# main.net
KiCad netlist of a schematic drawn in EAGLE
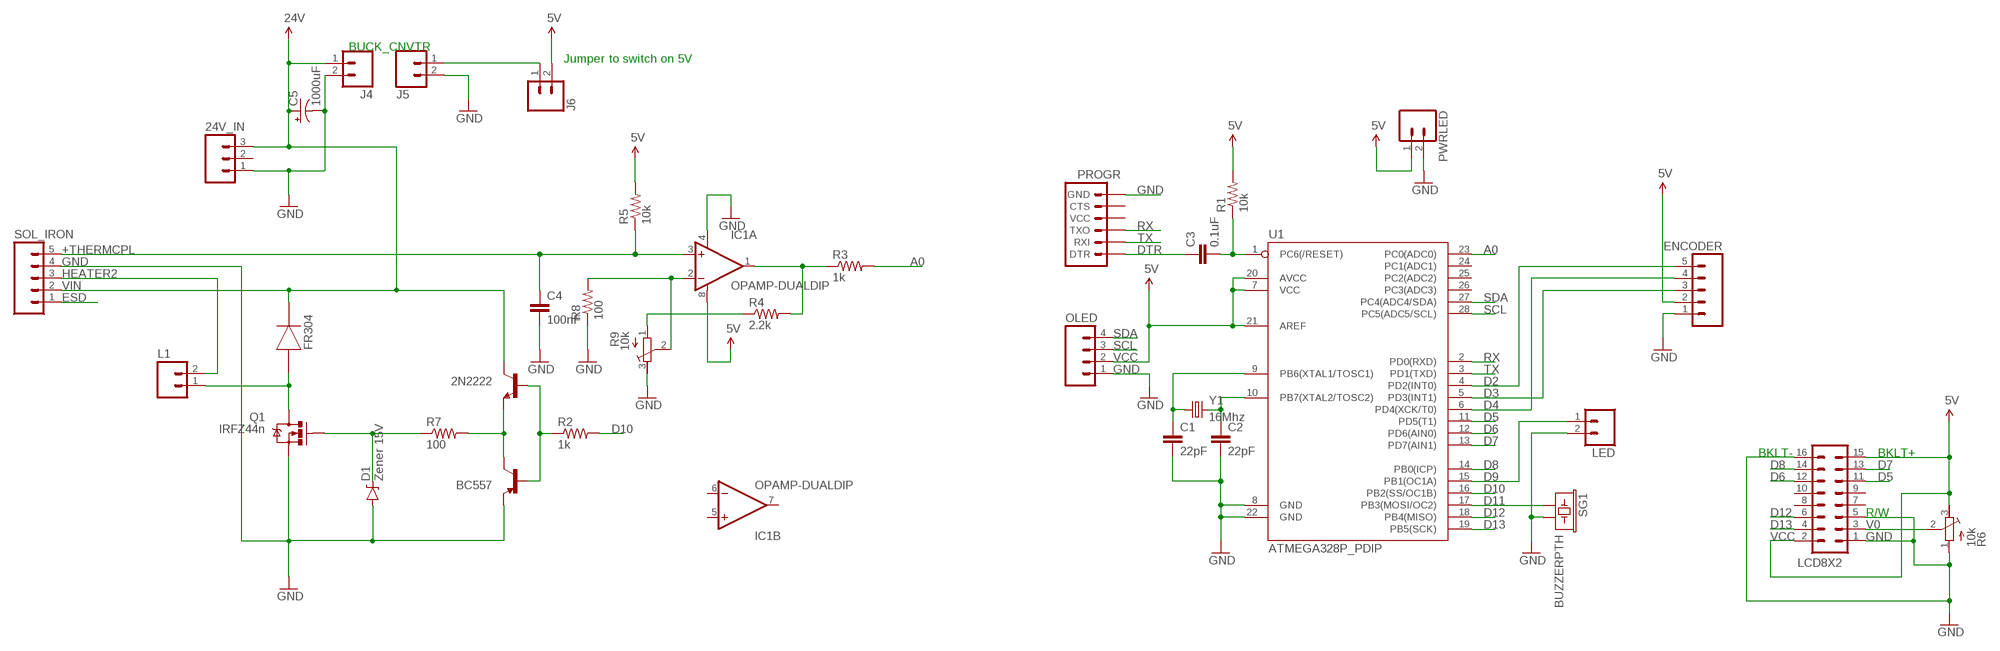
[diagram p0: schematic, sheet 1]

(export (version "E")
  (design (tool "Eeschema 10.0.6"))
  (components
    (comp (ref "2N2222")
      (value "TRANSISTOR_NPNP2N2222A")
      (footprint "eagle-import:TO-92")
      (libsource (lib "eagle-import") (part "TRANSISTOR_NPNP2N2222A"))
    )
    (comp (ref "24V_IN")
      (value "M03PTH")
      (footprint "eagle-import:1X03")
      (libsource (lib "eagle-import") (part "M03PTH"))
    )
    (comp (ref "BC557")
      (value "TRANSISTOR_PNPTO92")
      (footprint "eagle-import:TO-92")
      (libsource (lib "eagle-import") (part "TRANSISTOR_PNPTO92"))
    )
    (comp (ref "C1")
      (value "22pF")
      (footprint "eagle-import:CAP-PTH-SMALL")
      (libsource (lib "eagle-import") (part "CAPPTH"))
    )
    (comp (ref "C2")
      (value "22pF")
      (footprint "eagle-import:CAP-PTH-SMALL")
      (libsource (lib "eagle-import") (part "CAPPTH"))
    )
    (comp (ref "C3")
      (value "0.1uF")
      (footprint "eagle-import:CAP-PTH-SMALL")
      (libsource (lib "eagle-import") (part "CAPPTH"))
    )
    (comp (ref "C4")
      (value "100nF")
      (footprint "eagle-import:CAP-PTH-SMALL")
      (libsource (lib "eagle-import") (part "CAPPTH"))
    )
    (comp (ref "C5")
      (value "1000uF")
      (footprint "eagle-import:CPOL-RADIAL-1000UF-25V")
      (libsource (lib "eagle-import") (part "CAP_POLPTH4"))
    )
    (comp (ref "D1")
      (value "Zener 15V")
      (footprint "eagle-import:DIODE-ZENER")
      (libsource (lib "eagle-import") (part "DIODE-ZENERPTH"))
    )
    (comp (ref "ENCODER")
      (value "M05PTH")
      (footprint "eagle-import:1X05")
      (libsource (lib "eagle-import") (part "M05PTH"))
    )
    (comp (ref "IC1")
      (value "OPAMP-DUALDIP")
      (footprint "eagle-import:DIP08")
      (libsource (lib "eagle-import") (part "OPAMP-DUALDIP"))
    )
    (comp (ref "J4")
      (value "M02PTH")
      (footprint "eagle-import:1X02")
      (libsource (lib "eagle-import") (part "M02PTH"))
    )
    (comp (ref "J5")
      (value "M02PTH")
      (footprint "eagle-import:1X02")
      (libsource (lib "eagle-import") (part "M02PTH"))
    )
    (comp (ref "J6")
      (value "M02PTH")
      (footprint "eagle-import:1X02")
      (libsource (lib "eagle-import") (part "M02PTH"))
    )
    (comp (ref "L1")
      (value "M02PTH")
      (footprint "eagle-import:1X02")
      (libsource (lib "eagle-import") (part "M02PTH"))
    )
    (comp (ref "LCD8X2")
      (value "M08X2")
      (footprint "eagle-import:2X8")
      (libsource (lib "eagle-import") (part "M08X2"))
    )
    (comp (ref "LED")
      (value "M02PTH")
      (footprint "eagle-import:1X02")
      (libsource (lib "eagle-import") (part "M02PTH"))
    )
    (comp (ref "OLED")
      (value "M04PTH")
      (footprint "eagle-import:1X04")
      (libsource (lib "eagle-import") (part "M04PTH"))
    )
    (comp (ref "PROGR")
      (value "ARDUINO_SERIAL_PROGRAMPTH")
      (footprint "eagle-import:1X06")
      (libsource (lib "eagle-import") (part "ARDUINO_SERIAL_PROGRAMPTH"))
    )
    (comp (ref "PWRLED")
      (value "M02PTH")
      (footprint "eagle-import:1X02")
      (libsource (lib "eagle-import") (part "M02PTH"))
    )
    (comp (ref "Q1")
      (value "IRFZ44n")
      (footprint "eagle-import:TO220V")
      (libsource (lib "eagle-import") (part "MOSFET-NCHANNELFQP30N06L"))
    )
    (comp (ref "R1")
      (value "10k")
      (footprint "eagle-import:AXIAL-0.4")
      (libsource (lib "eagle-import") (part "RESISTORPTH-1/4W"))
    )
    (comp (ref "R2")
      (value "1k")
      (footprint "eagle-import:AXIAL-0.4")
      (libsource (lib "eagle-import") (part "RESISTORPTH-1/4W"))
    )
    (comp (ref "R3")
      (value "1k")
      (footprint "eagle-import:AXIAL-0.4")
      (libsource (lib "eagle-import") (part "RESISTORPTH-1/4W"))
    )
    (comp (ref "R4")
      (value "2.2k")
      (footprint "eagle-import:AXIAL-0.4")
      (libsource (lib "eagle-import") (part "RESISTORPTH-1/4W"))
    )
    (comp (ref "R5")
      (value "10k")
      (footprint "eagle-import:AXIAL-0.4")
      (libsource (lib "eagle-import") (part "RESISTORPTH-1/4W"))
    )
    (comp (ref "R6")
      (value "10k")
      (footprint "eagle-import:RTRIM3296W")
      (libsource (lib "eagle-import") (part "R-TRIMM3296W"))
    )
    (comp (ref "R7")
      (value "100")
      (footprint "eagle-import:AXIAL-0.4")
      (libsource (lib "eagle-import") (part "RESISTORPTH-1/4W"))
    )
    (comp (ref "R8")
      (value "100")
      (footprint "eagle-import:AXIAL-0.4")
      (libsource (lib "eagle-import") (part "RESISTORPTH-1/4W"))
    )
    (comp (ref "R9")
      (value "10k")
      (footprint "eagle-import:RTRIM3296W")
      (libsource (lib "eagle-import") (part "R-TRIMM3296W"))
    )
    (comp (ref "SG1")
      (value "BUZZERPTH")
      (footprint "eagle-import:BUZZER-12MM")
      (libsource (lib "eagle-import") (part "BUZZERPTH"))
    )
    (comp (ref "SOL_IRON")
      (value "M05PTH")
      (footprint "eagle-import:1X05")
      (libsource (lib "eagle-import") (part "M05PTH"))
    )
    (comp (ref "U$1")
      (value "FR304")
      (footprint "eagle-import:FR304")
      (libsource (lib "eagle-import") (part "FR304"))
    )
    (comp (ref "U1")
      (value "ATMEGA328P_PDIP")
      (footprint "eagle-import:DIL28-3")
      (libsource (lib "eagle-import") (part "ATMEGA328P_PDIP"))
    )
    (comp (ref "Y1")
      (value "16Mhz")
      (footprint "eagle-import:HC49US")
      (libsource (lib "eagle-import") (part "CRYSTALHC49US"))
    )
  )
  (nets
    (net (code "1") (name "/+THERMCPL") (class "Default")
      (node (ref "C4") (pin "1") (pinfunction "1_1") (pintype "passive"))
      (node (ref "IC1") (pin "3") (pinfunction "+IN_3") (pintype "input"))
      (node (ref "R5") (pin "P$1") (pinfunction "1_P$1") (pintype "passive"))
      (node (ref "SOL_IRON") (pin "5") (pinfunction "5_5") (pintype "passive"))
    )
    (net (code "2") (name "/A0") (class "Default")
      (node (ref "R3") (pin "P$2") (pinfunction "2_P$2") (pintype "passive"))
      (node (ref "U1") (pin "23") (pinfunction "PC0(ADC0)_23") (pintype "bidirectional"))
    )
    (net (code "3") (name "/D2") (class "Default")
      (node (ref "ENCODER") (pin "5") (pinfunction "5_5") (pintype "passive"))
      (node (ref "U1") (pin "4") (pinfunction "PD2(INT0)_4") (pintype "bidirectional"))
    )
    (net (code "4") (name "/D3") (class "Default")
      (node (ref "ENCODER") (pin "3") (pinfunction "3_3") (pintype "passive"))
      (node (ref "U1") (pin "5") (pinfunction "PD3(INT1)_5") (pintype "bidirectional"))
    )
    (net (code "5") (name "/D4") (class "Default")
      (node (ref "ENCODER") (pin "4") (pinfunction "4_4") (pintype "passive"))
      (node (ref "U1") (pin "6") (pinfunction "PD4(XCK/T0)_6") (pintype "bidirectional"))
    )
    (net (code "6") (name "/D5") (class "Default")
      (node (ref "LCD8X2") (pin "11") (pinfunction "11_11") (pintype "passive"))
      (node (ref "U1") (pin "11") (pinfunction "PD5(T1)_11") (pintype "bidirectional"))
    )
    (net (code "7") (name "/D6") (class "Default")
      (node (ref "LCD8X2") (pin "12") (pinfunction "12_12") (pintype "passive"))
      (node (ref "U1") (pin "12") (pinfunction "PD6(AIN0)_12") (pintype "bidirectional"))
    )
    (net (code "8") (name "/D7") (class "Default")
      (node (ref "LCD8X2") (pin "13") (pinfunction "13_13") (pintype "passive"))
      (node (ref "U1") (pin "13") (pinfunction "PD7(AIN1)_13") (pintype "bidirectional"))
    )
    (net (code "9") (name "/D8") (class "Default")
      (node (ref "LCD8X2") (pin "14") (pinfunction "14_14") (pintype "passive"))
      (node (ref "U1") (pin "14") (pinfunction "PB0(ICP)_14") (pintype "bidirectional"))
    )
    (net (code "10") (name "/D9") (class "Default")
      (node (ref "LED") (pin "1") (pinfunction "1_1") (pintype "passive"))
      (node (ref "U1") (pin "15") (pinfunction "PB1(OC1A)_15") (pintype "bidirectional"))
    )
    (net (code "11") (name "/D10") (class "Default")
      (node (ref "R2") (pin "P$2") (pinfunction "2_P$2") (pintype "passive"))
      (node (ref "U1") (pin "16") (pinfunction "PB2(SS/OC1B)_16") (pintype "bidirectional"))
    )
    (net (code "12") (name "/D11") (class "Default")
      (node (ref "SG1") (pin "+") (pinfunction "1_+") (pintype "passive"))
      (node (ref "U1") (pin "17") (pinfunction "PB3(MOSI/OC2)_17") (pintype "bidirectional"))
    )
    (net (code "13") (name "/D12") (class "Default")
      (node (ref "LCD8X2") (pin "6") (pinfunction "6_6") (pintype "passive"))
      (node (ref "U1") (pin "18") (pinfunction "PB4(MISO)_18") (pintype "bidirectional"))
    )
    (net (code "14") (name "/D13") (class "Default")
      (node (ref "LCD8X2") (pin "4") (pinfunction "4_4") (pintype "passive"))
      (node (ref "U1") (pin "19") (pinfunction "PB5(SCK)_19") (pintype "bidirectional"))
    )
    (net (code "15") (name "/DTR") (class "Default")
      (node (ref "C3") (pin "1") (pinfunction "1_1") (pintype "passive"))
      (node (ref "PROGR") (pin "1") (pinfunction "DTR_1") (pintype "passive"))
    )
    (net (code "16") (name "/ESD") (class "Default")
      (node (ref "SOL_IRON") (pin "1") (pinfunction "1_1") (pintype "passive"))
    )
    (net (code "17") (name "/HEATER2") (class "Default")
      (node (ref "L1") (pin "2") (pinfunction "2_2") (pintype "passive"))
      (node (ref "SOL_IRON") (pin "3") (pinfunction "3_3") (pintype "passive"))
    )
    (net (code "18") (name "/RX") (class "Default")
      (node (ref "PROGR") (pin "3") (pinfunction "TXO_3") (pintype "passive"))
      (node (ref "U1") (pin "2") (pinfunction "PD0(RXD)_2") (pintype "bidirectional"))
    )
    (net (code "19") (name "/SCL") (class "Default")
      (node (ref "OLED") (pin "3") (pinfunction "3_3") (pintype "passive"))
      (node (ref "U1") (pin "28") (pinfunction "PC5(ADC5/SCL)_28") (pintype "bidirectional"))
    )
    (net (code "20") (name "/SDA") (class "Default")
      (node (ref "OLED") (pin "4") (pinfunction "4_4") (pintype "passive"))
      (node (ref "U1") (pin "27") (pinfunction "PC4(ADC4/SDA)_27") (pintype "bidirectional"))
    )
    (net (code "21") (name "/TX") (class "Default")
      (node (ref "PROGR") (pin "2") (pinfunction "RXI_2") (pintype "passive"))
      (node (ref "U1") (pin "3") (pinfunction "PD1(TXD)_3") (pintype "bidirectional"))
    )
    (net (code "22") (name "/V0") (class "Default")
      (node (ref "LCD8X2") (pin "3") (pinfunction "3_3") (pintype "passive"))
      (node (ref "R6") (pin "2") (pinfunction "S_2") (pintype "passive"))
    )
    (net (code "23") (name "5V") (class "Default")
      (node (ref "ENCODER") (pin "2") (pinfunction "2_2") (pintype "passive"))
      (node (ref "IC1") (pin "8") (pinfunction "V+_8") (pintype "power_in"))
      (node (ref "J6") (pin "2") (pinfunction "2_2") (pintype "passive"))
      (node (ref "LCD8X2") (pin "15") (pinfunction "15_15") (pintype "passive"))
      (node (ref "LCD8X2") (pin "2") (pinfunction "2_2") (pintype "passive"))
      (node (ref "OLED") (pin "2") (pinfunction "2_2") (pintype "passive"))
      (node (ref "PWRLED") (pin "1") (pinfunction "1_1") (pintype "passive"))
      (node (ref "R1") (pin "P$2") (pinfunction "2_P$2") (pintype "passive"))
      (node (ref "R5") (pin "P$2") (pinfunction "2_P$2") (pintype "passive"))
      (node (ref "R6") (pin "3") (pinfunction "E_3") (pintype "passive"))
      (node (ref "U1") (pin "20") (pinfunction "AVCC_20") (pintype "bidirectional"))
      (node (ref "U1") (pin "21") (pinfunction "AREF_21") (pintype "bidirectional"))
      (node (ref "U1") (pin "7") (pinfunction "VCC_7") (pintype "bidirectional"))
    )
    (net (code "24") (name "24V") (class "Default")
      (node (ref "24V_IN") (pin "3") (pinfunction "3_3") (pintype "passive"))
      (node (ref "2N2222") (pin "1") (pinfunction "C_1") (pintype "passive"))
      (node (ref "C5") (pin "+") (pinfunction "+_+") (pintype "passive"))
      (node (ref "J4") (pin "1") (pinfunction "1_1") (pintype "passive"))
      (node (ref "SOL_IRON") (pin "2") (pinfunction "2_2") (pintype "passive"))
      (node (ref "U$1") (pin "K") (pinfunction "CATHODE_K") (pintype "bidirectional"))
    )
    (net (code "25") (name "GND") (class "Default")
      (node (ref "24V_IN") (pin "1") (pinfunction "1_1") (pintype "passive"))
      (node (ref "BC557") (pin "1") (pinfunction "E_1") (pintype "passive"))
      (node (ref "C1") (pin "2") (pinfunction "2_2") (pintype "passive"))
      (node (ref "C2") (pin "2") (pinfunction "2_2") (pintype "passive"))
      (node (ref "C4") (pin "2") (pinfunction "2_2") (pintype "passive"))
      (node (ref "C5") (pin "-") (pinfunction "-_-") (pintype "passive"))
      (node (ref "D1") (pin "P$2") (pinfunction "A_P$2") (pintype "passive"))
      (node (ref "ENCODER") (pin "1") (pinfunction "1_1") (pintype "passive"))
      (node (ref "IC1") (pin "4") (pinfunction "V-_4") (pintype "power_in"))
      (node (ref "J4") (pin "2") (pinfunction "2_2") (pintype "passive"))
      (node (ref "J5") (pin "2") (pinfunction "2_2") (pintype "passive"))
      (node (ref "LCD8X2") (pin "1") (pinfunction "1_1") (pintype "passive"))
      (node (ref "LCD8X2") (pin "16") (pinfunction "16_16") (pintype "passive"))
      (node (ref "LCD8X2") (pin "5") (pinfunction "5_5") (pintype "passive"))
      (node (ref "LED") (pin "2") (pinfunction "2_2") (pintype "passive"))
      (node (ref "OLED") (pin "1") (pinfunction "1_1") (pintype "passive"))
      (node (ref "PROGR") (pin "6") (pinfunction "GND_6") (pintype "passive"))
      (node (ref "PWRLED") (pin "2") (pinfunction "2_2") (pintype "passive"))
      (node (ref "Q1") (pin "3") (pinfunction "S_3") (pintype "passive"))
      (node (ref "R6") (pin "1") (pinfunction "A_1") (pintype "passive"))
      (node (ref "R8") (pin "P$1") (pinfunction "1_P$1") (pintype "passive"))
      (node (ref "R9") (pin "3") (pinfunction "E_3") (pintype "passive"))
      (node (ref "SG1") (pin "-") (pinfunction "2_-") (pintype "passive"))
      (node (ref "SOL_IRON") (pin "4") (pinfunction "4_4") (pintype "passive"))
      (node (ref "U1") (pin "22") (pinfunction "GND_22") (pintype "bidirectional"))
      (node (ref "U1") (pin "8") (pinfunction "GND_8") (pintype "bidirectional"))
    )
    (net (code "26") (name "Net-(2N2222-B)") (class "Default")
      (node (ref "2N2222") (pin "2") (pinfunction "B_2") (pintype "passive"))
      (node (ref "BC557") (pin "2") (pinfunction "B_2") (pintype "passive"))
      (node (ref "R2") (pin "P$1") (pinfunction "1_P$1") (pintype "passive"))
    )
    (net (code "27") (name "Net-(2N2222-E)") (class "Default")
      (node (ref "2N2222") (pin "3") (pinfunction "E_3") (pintype "passive"))
      (node (ref "BC557") (pin "3") (pinfunction "C_3") (pintype "passive"))
      (node (ref "R7") (pin "P$2") (pinfunction "2_P$2") (pintype "passive"))
    )
    (net (code "28") (name "Net-(D1-C)") (class "Default")
      (node (ref "D1") (pin "P$1") (pinfunction "C_P$1") (pintype "passive"))
      (node (ref "Q1") (pin "1") (pinfunction "G_1") (pintype "passive"))
      (node (ref "R7") (pin "P$1") (pinfunction "1_P$1") (pintype "passive"))
    )
    (net (code "29") (name "Net-(IC1A--IN)") (class "Default")
      (node (ref "IC1") (pin "2") (pinfunction "-IN_2") (pintype "input"))
      (node (ref "R8") (pin "P$2") (pinfunction "2_P$2") (pintype "passive"))
      (node (ref "R9") (pin "2") (pinfunction "S_2") (pintype "passive"))
    )
    (net (code "30") (name "Net-(IC1A-OUT)") (class "Default")
      (node (ref "IC1") (pin "1") (pinfunction "OUT_1") (pintype "output"))
      (node (ref "R3") (pin "P$1") (pinfunction "1_P$1") (pintype "passive"))
      (node (ref "R4") (pin "P$2") (pinfunction "2_P$2") (pintype "passive"))
    )
    (net (code "31") (name "Net-(J5-Pad1)") (class "Default")
      (node (ref "J5") (pin "1") (pinfunction "1_1") (pintype "passive"))
      (node (ref "J6") (pin "1") (pinfunction "1_1") (pintype "passive"))
    )
    (net (code "32") (name "Net-(Q1-D)") (class "Default")
      (node (ref "L1") (pin "1") (pinfunction "1_1") (pintype "passive"))
      (node (ref "Q1") (pin "2") (pinfunction "D_2") (pintype "passive"))
      (node (ref "U$1") (pin "A") (pinfunction "ANODE_A") (pintype "bidirectional"))
    )
    (net (code "33") (name "Net-(R1-1)") (class "Default")
      (node (ref "C3") (pin "2") (pinfunction "2_2") (pintype "passive"))
      (node (ref "R1") (pin "P$1") (pinfunction "1_P$1") (pintype "passive"))
      (node (ref "U1") (pin "1") (pinfunction "PC6(/RESET)_1") (pintype "bidirectional"))
    )
    (net (code "34") (name "Net-(R4-1)") (class "Default")
      (node (ref "R4") (pin "P$1") (pinfunction "1_P$1") (pintype "passive"))
      (node (ref "R9") (pin "1") (pinfunction "A_1") (pintype "passive"))
    )
    (net (code "35") (name "Net-(U1-PB6(XTAL1{slash}TOSC1))") (class "Default")
      (node (ref "C1") (pin "1") (pinfunction "1_1") (pintype "passive"))
      (node (ref "U1") (pin "9") (pinfunction "PB6(XTAL1/TOSC1)_9") (pintype "bidirectional"))
      (node (ref "Y1") (pin "1") (pinfunction "1_1") (pintype "passive"))
    )
    (net (code "36") (name "Net-(U1-PB7(XTAL2{slash}TOSC2))") (class "Default")
      (node (ref "C2") (pin "1") (pinfunction "1_1") (pintype "passive"))
      (node (ref "U1") (pin "10") (pinfunction "PB7(XTAL2/TOSC2)_10") (pintype "bidirectional"))
      (node (ref "Y1") (pin "2") (pinfunction "2_2") (pintype "passive"))
    )
    (net (code "37") (name "unconnected-(24V_IN-Pad2)") (class "Default")
      (node (ref "24V_IN") (pin "2") (pinfunction "2_2") (pintype "passive"))
    )
    (net (code "38") (name "unconnected-(IC1B-+IN-Pad5)") (class "Default")
      (node (ref "IC1") (pin "5") (pinfunction "+IN_5") (pintype "input"))
    )
    (net (code "39") (name "unconnected-(IC1B--IN-Pad6)") (class "Default")
      (node (ref "IC1") (pin "6") (pinfunction "-IN_6") (pintype "input"))
    )
    (net (code "40") (name "unconnected-(IC1B-OUT-Pad7)") (class "Default")
      (node (ref "IC1") (pin "7") (pinfunction "OUT_7") (pintype "output"))
    )
    (net (code "41") (name "unconnected-(LCD8X2-Pad7)") (class "Default")
      (node (ref "LCD8X2") (pin "7") (pinfunction "7_7") (pintype "passive"))
    )
    (net (code "42") (name "unconnected-(LCD8X2-Pad8)") (class "Default")
      (node (ref "LCD8X2") (pin "8") (pinfunction "8_8") (pintype "passive"))
    )
    (net (code "43") (name "unconnected-(LCD8X2-Pad9)") (class "Default")
      (node (ref "LCD8X2") (pin "9") (pinfunction "9_9") (pintype "passive"))
    )
    (net (code "44") (name "unconnected-(LCD8X2-Pad10)") (class "Default")
      (node (ref "LCD8X2") (pin "10") (pinfunction "10_10") (pintype "passive"))
    )
    (net (code "45") (name "unconnected-(PROGR-CTS-Pad5)") (class "Default")
      (node (ref "PROGR") (pin "5") (pinfunction "CTS_5") (pintype "passive"))
    )
    (net (code "46") (name "unconnected-(PROGR-VCC-Pad4)") (class "Default")
      (node (ref "PROGR") (pin "4") (pinfunction "VCC_4") (pintype "passive"))
    )
    (net (code "47") (name "unconnected-(U1-PC1(ADC1)-Pad24)") (class "Default")
      (node (ref "U1") (pin "24") (pinfunction "PC1(ADC1)_24") (pintype "bidirectional"))
    )
    (net (code "48") (name "unconnected-(U1-PC2(ADC2)-Pad25)") (class "Default")
      (node (ref "U1") (pin "25") (pinfunction "PC2(ADC2)_25") (pintype "bidirectional"))
    )
    (net (code "49") (name "unconnected-(U1-PC3(ADC3)-Pad26)") (class "Default")
      (node (ref "U1") (pin "26") (pinfunction "PC3(ADC3)_26") (pintype "bidirectional"))
    )
  )
)
